# Buffer_EXC.net
KiCad netlist of a schematic drawn in Altium Designer
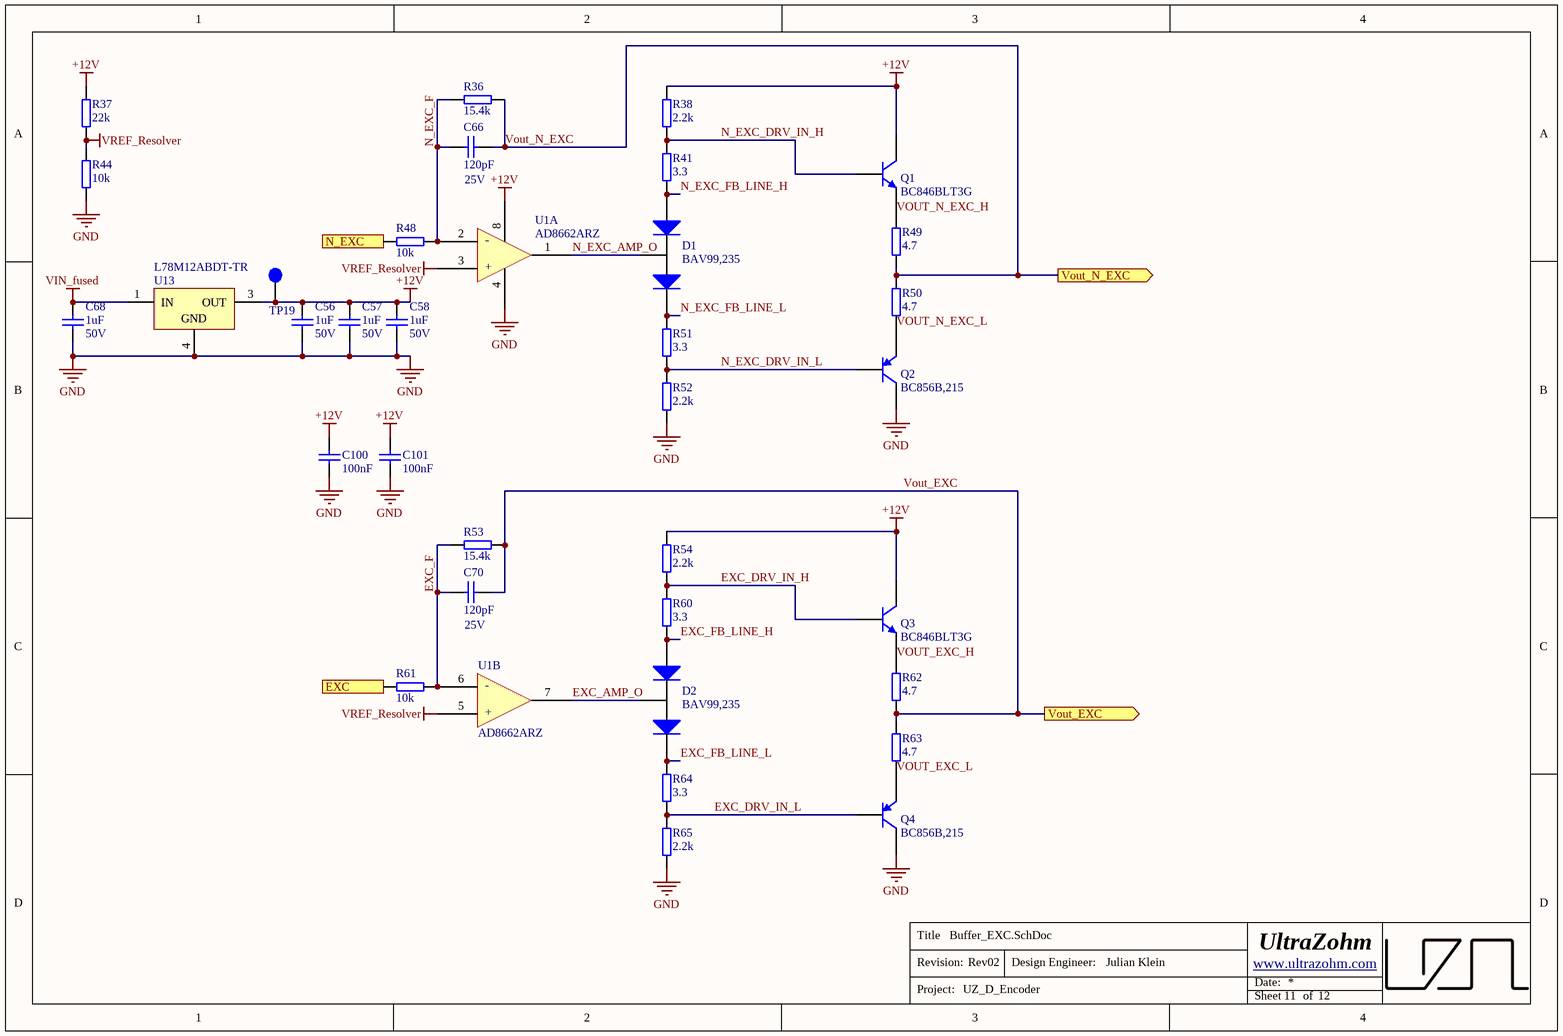
[diagram p0: Buffer_EXC.SchDoc]

(export (version "E")
  (design (tool "Eeschema 10.0.6"))
  (components
    (comp (ref "C56")
      (value "1uF")
      (footprint "RES_1206")
      (description "Capacitor")
      (fields (field (name "VOLTAGE") "50V"))
      (libsource (lib "Componentes_SOC") (part "Cap_1206"))
    )
    (comp (ref "C57")
      (value "1uF")
      (footprint "RES_1206")
      (description "Capacitor")
      (fields (field (name "VOLTAGE") "50V"))
      (libsource (lib "Componentes_SOC") (part "Cap_1206"))
    )
    (comp (ref "C58")
      (value "1uF")
      (footprint "RES_1206")
      (description "Capacitor")
      (fields (field (name "VOLTAGE") "50V"))
      (libsource (lib "Componentes_SOC") (part "Cap_1206"))
    )
    (comp (ref "C66")
      (value "120pF")
      (footprint "CAPC1608X07N")
      (fields (field (name "VOLTAGE") "25V"))
      (libsource (lib "UltraZohm_ADC") (part "Cap_0603"))
    )
    (comp (ref "C68")
      (value "1uF")
      (footprint "RES_1206")
      (description "Capacitor")
      (fields (field (name "VOLTAGE") "50V"))
      (libsource (lib "Componentes_SOC") (part "Cap_1206"))
    )
    (comp (ref "C70")
      (value "120pF")
      (footprint "CAPC1608X07N")
      (fields (field (name "VOLTAGE") "25V"))
      (libsource (lib "UltraZohm_ADC") (part "Cap_0603"))
    )
    (comp (ref "C100")
      (value "100nF")
      (footprint "CAPC1608X07N")
      (fields (field (name "MF") "Würth") (field (name "MPN") "885012206071") (field (name "VOLTAGE") "25V"))
      (libsource (lib "UltraZohm_ADC") (part "Cap_0603"))
    )
    (comp (ref "C101")
      (value "100nF")
      (footprint "CAPC1608X07N")
      (fields (field (name "MF") "Würth") (field (name "MPN") "885012206071") (field (name "VOLTAGE") "25V"))
      (libsource (lib "UltraZohm_ADC") (part "Cap_0603"))
    )
    (comp (ref "D1")
      (value "BAV99,235")
      (footprint "SOT-23")
      (description "DIODE ARRAY GP 100V 215MA SOT23")
      (fields (field (name "MF") "Nexperia"))
      (libsource (lib "Componentes_SOC") (part "Diode Array"))
    )
    (comp (ref "D2")
      (value "BAV99,235")
      (footprint "SOT-23")
      (description "DIODE ARRAY GP 100V 215MA SOT23")
      (fields (field (name "MF") "Nexperia"))
      (libsource (lib "Componentes_SOC") (part "Diode Array"))
    )
    (comp (ref "Q1")
      (value "BC846BLT3G")
      (footprint "SOT-23")
      (description "NPN Bipolar Transistor")
      (fields (field (name "MF") "ON Semiconductor"))
      (libsource (lib "Componentes_SOC") (part "NPN Transistor BC846"))
    )
    (comp (ref "Q2")
      (value "BC856B,215")
      (footprint "SOT-23")
      (description "PNP Bipolar Transistor")
      (fields (field (name "MF") "Nexperia"))
      (libsource (lib "Componentes_SOC") (part "PNP Transistor BC846"))
    )
    (comp (ref "Q3")
      (value "BC846BLT3G")
      (footprint "SOT-23")
      (description "NPN Bipolar Transistor")
      (fields (field (name "MF") "ON Semiconductor"))
      (libsource (lib "Componentes_SOC") (part "NPN Transistor BC846"))
    )
    (comp (ref "Q4")
      (value "BC856B,215")
      (footprint "SOT-23")
      (description "PNP Bipolar Transistor")
      (fields (field (name "MF") "Nexperia"))
      (libsource (lib "Componentes_SOC") (part "PNP Transistor BC846"))
    )
    (comp (ref "R36")
      (value "15.4k")
      (footprint "RESC1608X06N")
      (fields (field (name "MF") "Vishay") (field (name "MPN") "CRCW06030000Z0EAC"))
      (libsource (lib "UltraZohm_ADC") (part "R_0603"))
    )
    (comp (ref "R37")
      (value "22k")
      (footprint "RESC1608X06N")
      (libsource (lib "UltraZohm_ADC") (part "R_0603"))
    )
    (comp (ref "R38")
      (value "2.2k")
      (footprint "RESC1608X06N")
      (fields (field (name "MF") "Vishay") (field (name "MPN") "CRCW06030000Z0EAC"))
      (libsource (lib "UltraZohm_ADC") (part "R_0603"))
    )
    (comp (ref "R41")
      (value "3.3")
      (footprint "RESC1608X06N")
      (fields (field (name "MF") "Vishay") (field (name "MPN") "CRCW06030000Z0EAC"))
      (libsource (lib "UltraZohm_ADC") (part "R_0603"))
    )
    (comp (ref "R44")
      (value "10k")
      (footprint "RESC1608X06N")
      (fields (field (name "MF") "Vishay") (field (name "MPN") "CRCW06030000Z0EAC"))
      (libsource (lib "UltraZohm_ADC") (part "R_0603"))
    )
    (comp (ref "R48")
      (value "10k")
      (footprint "RESC1608X06N")
      (fields (field (name "MF") "Vishay") (field (name "MPN") "CRCW06030000Z0EAC"))
      (libsource (lib "UltraZohm_ADC") (part "R_0603"))
    )
    (comp (ref "R49")
      (value "4.7")
      (footprint "RESC1608X06N")
      (fields (field (name "MF") "Vishay"))
      (libsource (lib "UltraZohm_ADC") (part "R_0603"))
    )
    (comp (ref "R50")
      (value "4.7")
      (footprint "RESC1608X06N")
      (fields (field (name "MF") "Vishay"))
      (libsource (lib "UltraZohm_ADC") (part "R_0603"))
    )
    (comp (ref "R51")
      (value "3.3")
      (footprint "RESC1608X06N")
      (fields (field (name "MF") "Vishay") (field (name "MPN") "CRCW06030000Z0EAC"))
      (libsource (lib "UltraZohm_ADC") (part "R_0603"))
    )
    (comp (ref "R52")
      (value "2.2k")
      (footprint "RESC1608X06N")
      (fields (field (name "MF") "Vishay") (field (name "MPN") "CRCW06030000Z0EAC"))
      (libsource (lib "UltraZohm_ADC") (part "R_0603"))
    )
    (comp (ref "R53")
      (value "15.4k")
      (footprint "RESC1608X06N")
      (fields (field (name "MF") "Vishay") (field (name "MPN") "CRCW06030000Z0EAC"))
      (libsource (lib "UltraZohm_ADC") (part "R_0603"))
    )
    (comp (ref "R54")
      (value "2.2k")
      (footprint "RESC1608X06N")
      (fields (field (name "MF") "Vishay") (field (name "MPN") "CRCW06030000Z0EAC"))
      (libsource (lib "UltraZohm_ADC") (part "R_0603"))
    )
    (comp (ref "R60")
      (value "3.3")
      (footprint "RESC1608X06N")
      (fields (field (name "MF") "Vishay") (field (name "MPN") "CRCW06030000Z0EAC"))
      (libsource (lib "UltraZohm_ADC") (part "R_0603"))
    )
    (comp (ref "R61")
      (value "10k")
      (footprint "RESC1608X06N")
      (fields (field (name "MF") "Vishay") (field (name "MPN") "CRCW06030000Z0EAC"))
      (libsource (lib "UltraZohm_ADC") (part "R_0603"))
    )
    (comp (ref "R62")
      (value "4.7")
      (footprint "RESC1608X06N")
      (fields (field (name "MF") "Vishay"))
      (libsource (lib "UltraZohm_ADC") (part "R_0603"))
    )
    (comp (ref "R63")
      (value "4.7")
      (footprint "RESC1608X06N")
      (fields (field (name "MF") "Vishay"))
      (libsource (lib "UltraZohm_ADC") (part "R_0603"))
    )
    (comp (ref "R64")
      (value "3.3")
      (footprint "RESC1608X06N")
      (fields (field (name "MF") "Vishay") (field (name "MPN") "CRCW06030000Z0EAC"))
      (libsource (lib "UltraZohm_ADC") (part "R_0603"))
    )
    (comp (ref "R65")
      (value "2.2k")
      (footprint "RESC1608X06N")
      (fields (field (name "MF") "Vishay") (field (name "MPN") "CRCW06030000Z0EAC"))
      (libsource (lib "UltraZohm_ADC") (part "R_0603"))
    )
    (comp (ref "TP19")
      (value "VCC")
      (footprint "TP_1mm")
      (description "Testpoint 1mm")
      (fields (field (name "CREATED") "2018_06_25_AGeiger"))
      (libsource (lib "UltraZOhm_CarrierBoard") (part "TP_1mm"))
    )
    (comp (ref "U1")
      (value "AD8662ARZ")
      (footprint "SOIC8_N")
      (description "IC OPAMP GP 2 CIRCUIT 14SOIC")
      (fields (field (name "MF") "Analog Devices"))
      (libsource (lib "Componentes_SOC") (part "AD8662"))
    )
    (comp (ref "U13")
      (value "L78M12ABDT-TR")
      (footprint "TO-252_M")
      (description "Precision 500mA Regulator, 12V, 3-Pin DPAK, Tape and Reel")
      (libsource (lib "Altium Content Vault") (part "PM-REG-L4940-SOT3"))
    )
  )
  (nets
    (net (code "1") (name "+12V") (class "Default")
      (node (ref "C100") (pin "1") (pinfunction "1_1") (pintype "passive"))
      (node (ref "C101") (pin "1") (pinfunction "1_1") (pintype "passive"))
      (node (ref "C56") (pin "1") (pinfunction "1_1") (pintype "passive"))
      (node (ref "C57") (pin "1") (pinfunction "1_1") (pintype "passive"))
      (node (ref "C58") (pin "1") (pinfunction "1_1") (pintype "passive"))
      (node (ref "Q1") (pin "3") (pinfunction "C_3") (pintype "passive"))
      (node (ref "Q3") (pin "3") (pinfunction "C_3") (pintype "passive"))
      (node (ref "R37") (pin "2") (pintype "passive"))
      (node (ref "R38") (pin "2") (pintype "passive"))
      (node (ref "R54") (pin "2") (pintype "passive"))
      (node (ref "TP19") (pin "1") (pintype "passive"))
      (node (ref "U1") (pin "8") (pinfunction "v-_8") (pintype "passive"))
      (node (ref "U13") (pin "3") (pinfunction "OUT_3") (pintype "power_in"))
    )
    (net (code "2") (name "/EXC") (class "Default") (node (ref "R61") (pin "2") (pintype "passive")))
    (net (code "3") (name "/EXC_AMP_O") (class "Default")
      (node (ref "D2") (pin "3") (pintype "passive"))
      (node (ref "U1") (pin "7") (pinfunction "out_b_7") (pintype "passive"))
    )
    (net (code "4") (name "/EXC_DRV_IN_H") (class "Default")
      (node (ref "Q3") (pin "1") (pinfunction "B_1") (pintype "passive"))
      (node (ref "R54") (pin "1") (pintype "passive"))
      (node (ref "R60") (pin "2") (pintype "passive"))
    )
    (net (code "5") (name "/EXC_DRV_IN_L") (class "Default")
      (node (ref "Q4") (pin "1") (pinfunction "B_1") (pintype "passive"))
      (node (ref "R64") (pin "2") (pintype "passive"))
      (node (ref "R65") (pin "1") (pintype "passive"))
    )
    (net (code "6") (name "/EXC_F") (class "Default")
      (node (ref "C70") (pin "1") (pinfunction "1_1") (pintype "passive"))
      (node (ref "R53") (pin "1") (pintype "passive"))
      (node (ref "R61") (pin "1") (pintype "passive"))
      (node (ref "U1") (pin "6") (pinfunction "-in_b_6") (pintype "passive"))
    )
    (net (code "7") (name "/EXC_FB_LINE_H") (class "Default")
      (node (ref "D2") (pin "1") (pintype "passive"))
      (node (ref "R60") (pin "1") (pintype "passive"))
    )
    (net (code "8") (name "/EXC_FB_LINE_L") (class "Default")
      (node (ref "D2") (pin "2") (pintype "passive"))
      (node (ref "R64") (pin "1") (pintype "passive"))
    )
    (net (code "9") (name "/N_EXC") (class "Default") (node (ref "R48") (pin "2") (pintype "passive")))
    (net (code "10") (name "/N_EXC_AMP_O") (class "Default")
      (node (ref "D1") (pin "3") (pintype "passive"))
      (node (ref "U1") (pin "1") (pinfunction "out_a_1") (pintype "passive"))
    )
    (net (code "11") (name "/N_EXC_DRV_IN_H") (class "Default")
      (node (ref "Q1") (pin "1") (pinfunction "B_1") (pintype "passive"))
      (node (ref "R38") (pin "1") (pintype "passive"))
      (node (ref "R41") (pin "2") (pintype "passive"))
    )
    (net (code "12") (name "/N_EXC_DRV_IN_L") (class "Default")
      (node (ref "Q2") (pin "1") (pinfunction "B_1") (pintype "passive"))
      (node (ref "R51") (pin "2") (pintype "passive"))
      (node (ref "R52") (pin "1") (pintype "passive"))
    )
    (net (code "13") (name "/N_EXC_F") (class "Default")
      (node (ref "C66") (pin "1") (pinfunction "1_1") (pintype "passive"))
      (node (ref "R36") (pin "1") (pintype "passive"))
      (node (ref "R48") (pin "1") (pintype "passive"))
      (node (ref "U1") (pin "2") (pinfunction "-in_a_2") (pintype "passive"))
    )
    (net (code "14") (name "/N_EXC_FB_LINE_H") (class "Default")
      (node (ref "D1") (pin "1") (pintype "passive"))
      (node (ref "R41") (pin "1") (pintype "passive"))
    )
    (net (code "15") (name "/N_EXC_FB_LINE_L") (class "Default")
      (node (ref "D1") (pin "2") (pintype "passive"))
      (node (ref "R51") (pin "1") (pintype "passive"))
    )
    (net (code "16") (name "/VOUT_EXC_H") (class "Default")
      (node (ref "Q3") (pin "2") (pinfunction "E_2") (pintype "passive"))
      (node (ref "R62") (pin "1") (pintype "passive"))
    )
    (net (code "17") (name "/VOUT_EXC_L") (class "Default")
      (node (ref "Q4") (pin "2") (pinfunction "E_2") (pintype "passive"))
      (node (ref "R63") (pin "2") (pintype "passive"))
    )
    (net (code "18") (name "/VOUT_N_EXC_H") (class "Default")
      (node (ref "Q1") (pin "2") (pinfunction "E_2") (pintype "passive"))
      (node (ref "R49") (pin "1") (pintype "passive"))
    )
    (net (code "19") (name "/VOUT_N_EXC_L") (class "Default")
      (node (ref "Q2") (pin "2") (pinfunction "E_2") (pintype "passive"))
      (node (ref "R50") (pin "2") (pintype "passive"))
    )
    (net (code "20") (name "/Vout_EXC") (class "Default")
      (node (ref "C70") (pin "2") (pinfunction "2_2") (pintype "passive"))
      (node (ref "R53") (pin "2") (pintype "passive"))
      (node (ref "R62") (pin "2") (pintype "passive"))
      (node (ref "R63") (pin "1") (pintype "passive"))
    )
    (net (code "21") (name "/Vout_N_EXC") (class "Default")
      (node (ref "C66") (pin "2") (pinfunction "2_2") (pintype "passive"))
      (node (ref "R36") (pin "2") (pintype "passive"))
      (node (ref "R49") (pin "2") (pintype "passive"))
      (node (ref "R50") (pin "1") (pintype "passive"))
    )
    (net (code "22") (name "GND") (class "Default")
      (node (ref "C100") (pin "2") (pinfunction "2_2") (pintype "passive"))
      (node (ref "C101") (pin "2") (pinfunction "2_2") (pintype "passive"))
      (node (ref "C56") (pin "2") (pinfunction "2_2") (pintype "passive"))
      (node (ref "C57") (pin "2") (pinfunction "2_2") (pintype "passive"))
      (node (ref "C58") (pin "2") (pinfunction "2_2") (pintype "passive"))
      (node (ref "C68") (pin "2") (pinfunction "2_2") (pintype "passive"))
      (node (ref "Q2") (pin "3") (pinfunction "C_3") (pintype "passive"))
      (node (ref "Q4") (pin "3") (pinfunction "C_3") (pintype "passive"))
      (node (ref "R44") (pin "1") (pintype "passive"))
      (node (ref "R52") (pin "2") (pintype "passive"))
      (node (ref "R65") (pin "2") (pintype "passive"))
      (node (ref "U1") (pin "4") (pinfunction "v+_4") (pintype "passive"))
      (node (ref "U13") (pin "4") (pinfunction "GND_4") (pintype "power_in"))
    )
    (net (code "23") (name "VIN_fused") (class "Default")
      (node (ref "C68") (pin "1") (pinfunction "1_1") (pintype "passive"))
      (node (ref "U13") (pin "1") (pinfunction "IN_1") (pintype "power_in"))
    )
    (net (code "24") (name "VREF_Resolver") (class "Default")
      (node (ref "R37") (pin "1") (pintype "passive"))
      (node (ref "R44") (pin "2") (pintype "passive"))
      (node (ref "U1") (pin "3") (pinfunction "+in_a_3") (pintype "passive"))
      (node (ref "U1") (pin "5") (pinfunction "+in_b_5") (pintype "passive"))
    )
  )
)
